# Sheet2.net
KiCad netlist of a schematic drawn in Altium Designer
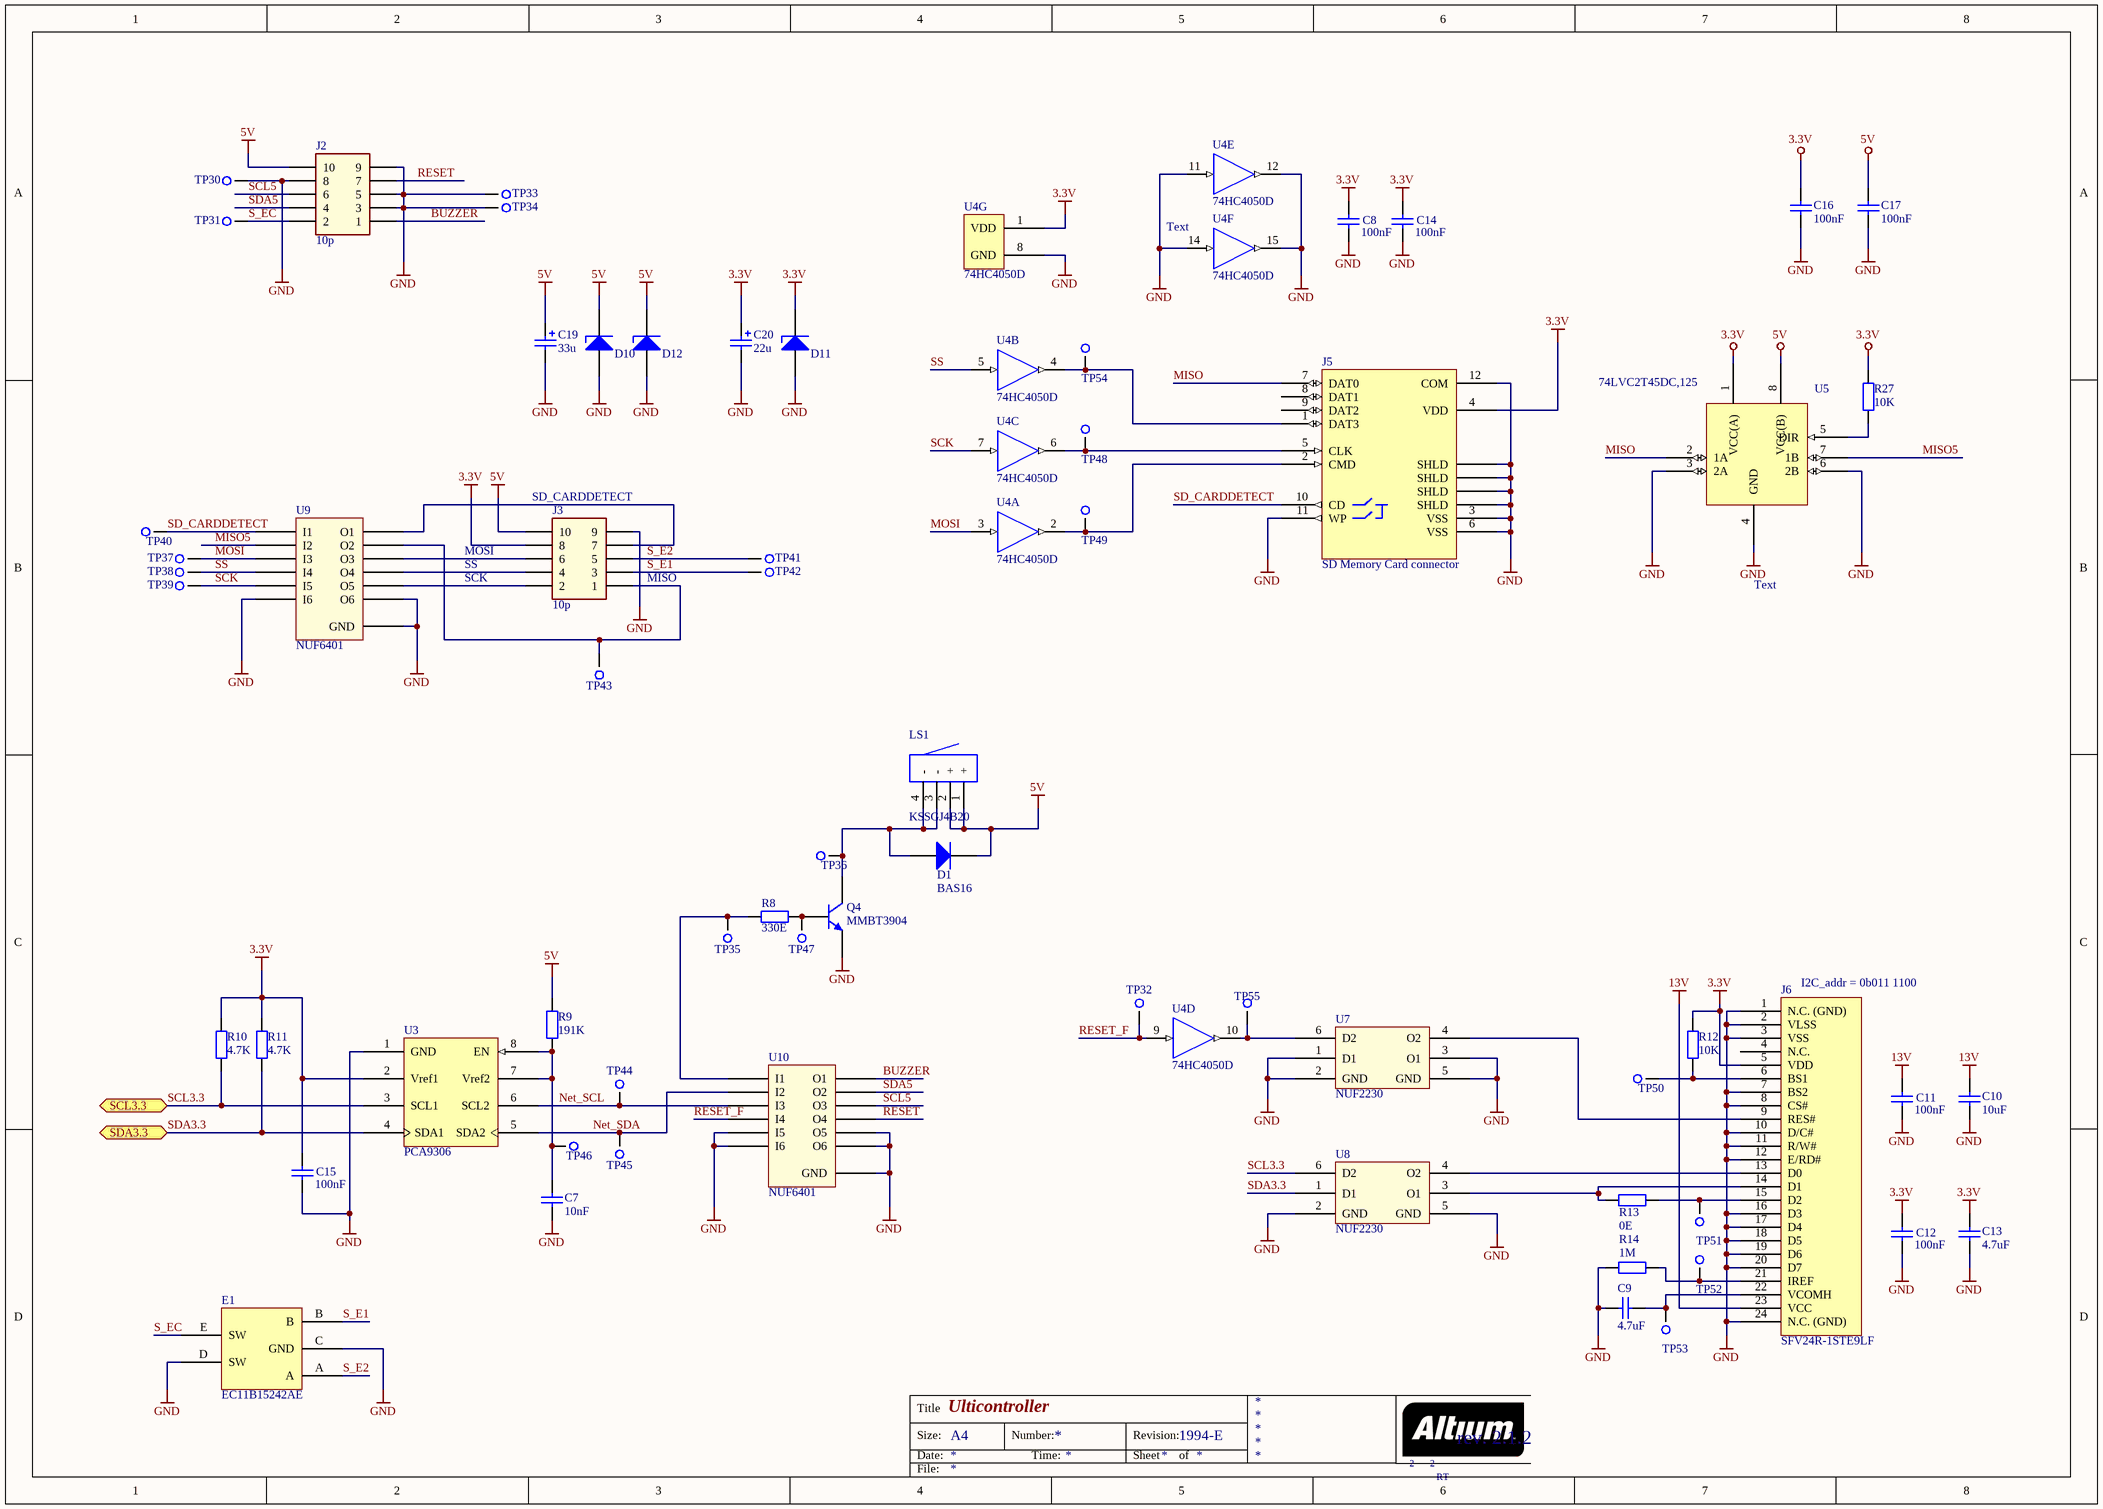
[diagram p0: Sheet2.SchDoc]

(export (version "E")
  (design (tool "Eeschema 10.0.6"))
  (components
    (comp (ref "C7")
      (value "10nF")
      (footprint "C0805 (2012)")
      (description "Cap 10nF X7R 0805 10% 100V")
      (fields (field (name "MFG") "AVX"))
      (libsource (lib "Faber_SCH_lib") (part "Cap 10nF X7R 0805"))
    )
    (comp (ref "C8")
      (value "100nF")
      (footprint "C0805 (2012)")
      (description "Cap 100nF X7R 0805 10% 100V")
      (fields (field (name "MFG") "AVX"))
      (libsource (lib "Faber_SCH_lib") (part "Cap 100nF X7R 0805"))
    )
    (comp (ref "C9")
      (value "4.7uF")
      (footprint "C1206 (3216)")
      (description "Cap 4.7uF 1206 X7R 10% 25V")
      (fields (field (name "MFG") "TDK"))
      (libsource (lib "Faber_SCH_lib") (part "Cap 4.7uF X7R 1206"))
    )
    (comp (ref "C10")
      (value "10uF")
      (footprint "C1206 (3216)")
      (description "Cap 10uF 1206 X7R 10% 25V")
      (fields (field (name "MFG") "KEMET"))
      (libsource (lib "Faber_SCH_lib") (part "Cap 10uF X7R 1206"))
    )
    (comp (ref "C11")
      (value "100nF")
      (footprint "C0805 (2012)")
      (description "Cap 100nF X7R 0805 10% 100V")
      (fields (field (name "MFG") "AVX"))
      (libsource (lib "Faber_SCH_lib") (part "Cap 100nF X7R 0805"))
    )
    (comp (ref "C12")
      (value "100nF")
      (footprint "C0805 (2012)")
      (description "Cap 100nF X7R 0805 10% 100V")
      (fields (field (name "MFG") "AVX"))
      (libsource (lib "Faber_SCH_lib") (part "Cap 100nF X7R 0805"))
    )
    (comp (ref "C13")
      (value "4.7uF")
      (footprint "C1206 (3216)")
      (description "Cap 4.7uF 1206 X7R 10% 25V")
      (fields (field (name "MFG") "TDK"))
      (libsource (lib "Faber_SCH_lib") (part "Cap 4.7uF X7R 1206"))
    )
    (comp (ref "C14")
      (value "100nF")
      (footprint "C0805 (2012)")
      (description "Cap 100nF X7R 0805 10% 100V")
      (fields (field (name "MFG") "AVX"))
      (libsource (lib "Faber_SCH_lib") (part "Cap 100nF X7R 0805"))
    )
    (comp (ref "C15")
      (value "100nF")
      (footprint "C0805 (2012)")
      (description "Cap 100nF X7R 0805 10% 100V")
      (fields (field (name "MFG") "AVX"))
      (libsource (lib "Faber_SCH_lib") (part "Cap 100nF X7R 0805"))
    )
    (comp (ref "C16")
      (value "100nF")
      (footprint "C0805 (2012)")
      (description "Cap 100nF X7R 0805 10% 100V")
      (fields (field (name "MFG") "AVX"))
      (libsource (lib "Faber_SCH_lib") (part "Cap 100nF X7R 0805"))
    )
    (comp (ref "C17")
      (value "100nF")
      (footprint "C0805 (2012)")
      (description "Cap 100nF X7R 0805 10% 100V")
      (fields (field (name "MFG") "AVX"))
      (libsource (lib "Faber_SCH_lib") (part "Cap 100nF X7R 0805"))
    )
    (comp (ref "C19")
      (value "33u")
      (footprint "CAPAE5543X61M")
      (description "CAP ALUM 33UF 20% 10V SMD")
      (fields (field (name "MFG") "Panasonic Electronic Components") (field (name "TOLERANCE") "±20%"))
      (libsource (lib "UltiController") (part "Cap 33uF"))
    )
    (comp (ref "C20")
      (value "22u")
      (footprint "CAPAE5543X61M")
      (description "CAP ALUM 22UF 20% 6.3V SMD")
      (fields (field (name "MFG") "Panasonic Electronic Components") (field (name "TOLERANCE") "±20%"))
      (libsource (lib "UltiController") (part "Cap 22uF"))
    )
    (comp (ref "D1")
      (value "BAS16")
      (footprint "IC SOT23")
      (description "Diode BAS16  SOT23 85V 215MA")
      (fields (field (name "MFG") "NXP"))
      (libsource (lib "Faber_SCH_lib") (part "Diode BAS16"))
    )
    (comp (ref "D10")
      (value "ESD9X5.0ST5G")
      (footprint "SODFL100X40-2N")
      (description "TVS DIODE 5VWM 12.3VC SOD923")
      (fields (field (name "MFG") "ON Semiconductor"))
      (libsource (lib "Olimex interface board") (part "ESD9X5.0ST5G"))
    )
    (comp (ref "D11")
      (value "ESD9X3.3ST5G")
      (footprint "SODFL100X40-2N")
      (description "TVS DIODE 3.3VWM 10.4VC SOD923")
      (fields (field (name "MFG") "ON Semiconductor"))
      (libsource (lib "Olimex interface board") (part "ESD9X3.3ST5G"))
    )
    (comp (ref "D12")
      (value "ESD9X5.0ST5G")
      (footprint "SODFL100X40-2N")
      (description "TVS DIODE 5VWM 12.3VC SOD923")
      (fields (field (name "MFG") "ON Semiconductor"))
      (libsource (lib "Olimex interface board") (part "ESD9X5.0ST5G"))
    )
    (comp (ref "E1")
      (value "EC11B15242AE")
      (footprint "Misc EC11B15242AE")
      (description "Misc EC11B15242AE encoder horiz")
      (fields (field (name "MFG") "ALPS"))
      (libsource (lib "Faber_SCH_lib") (part "Misc EC11B15242AE"))
    )
    (comp (ref "J2")
      (value "10p")
      (footprint "HEADER 10P right angle")
      (description "Header 2x5p right angle 2.54mm")
      (fields (field (name "MFG") "WURTH ELEKTRONIK"))
      (libsource (lib "Faber_SCH_lib") (part "Header 10p"))
    )
    (comp (ref "J3")
      (value "10p")
      (footprint "HEADER 10P right angle")
      (description "Header 2x5p right angle 2.54mm")
      (fields (field (name "MFG") "WURTH ELEKTRONIK"))
      (libsource (lib "Faber_SCH_lib") (part "Header 10p"))
    )
    (comp (ref "J5")
      (value "SD Memory Card connector")
      (footprint "CON SD-Card")
      (description "Connector Std,reverse SD Memory Card connector")
      (fields (field (name "MFG") "HRS (HIROSE)"))
      (libsource (lib "Faber_SCH_lib") (part "Connector SD-Card-Hirose"))
    )
    (comp (ref "J6")
      (value "SFV24R-1STE9LF")
      (footprint "Con SFV24R-1STE9LF")
      (description "Connector FPC/FFC 0.5mm R/A 24p SMD")
      (fields (field (name "MFG") "FCI"))
      (libsource (lib "Faber_SCH_lib") (part "Connector SFV24R-1STE9LF"))
    )
    (comp (ref "LS1")
      (value "KSSGJ4B20")
      (footprint "Buzzer KSSGJ4B20")
      (description "Buzzer KSSGJ4B20 SMD")
      (fields (field (name "MFG") "KINGSTATE"))
      (libsource (lib "Faber_SCH_lib") (part "Buzzer KSSGJ4B20"))
    )
    (comp (ref "Q4")
      (value "MMBT3904")
      (footprint "IC SOT23")
      (description "NPN MMBT3904 SOT-23 200mA")
      (fields (field (name "MFG") "NXP"))
      (libsource (lib "Faber_SCH_lib") (part "NPN MMBT3904"))
    )
    (comp (ref "R8")
      (value "330E")
      (footprint "R0805 (2012)")
      (description "Res 330E 0805 1% 100mW")
      (fields (field (name "MFG") "MULTICOMP"))
      (libsource (lib "Faber_SCH_lib") (part "Res 330E 0805"))
    )
    (comp (ref "R9")
      (value "191K")
      (footprint "R0805 (2012)")
      (description "Res 191K 0805 1% 125mW")
      (fields (field (name "MFG") "VISHAY DRALORIC"))
      (libsource (lib "Faber_SCH_lib") (part "Res 191K 0805"))
    )
    (comp (ref "R10")
      (value "4.7K")
      (footprint "R0805 (2012)")
      (description "Res 4.7K 0805 1% 100mW")
      (fields (field (name "MFG") "MULTICOMP"))
      (libsource (lib "Faber_SCH_lib") (part "Res 4.7K 0805"))
    )
    (comp (ref "R11")
      (value "4.7K")
      (footprint "R0805 (2012)")
      (description "Res 4.7K 0805 1% 100mW")
      (fields (field (name "MFG") "MULTICOMP"))
      (libsource (lib "Faber_SCH_lib") (part "Res 4.7K 0805"))
    )
    (comp (ref "R12")
      (value "10K")
      (footprint "R0805 (2012)")
      (description "Res 10K 0805 1% 100mW")
      (fields (field (name "MFG") "MULTICOMP"))
      (libsource (lib "Faber_SCH_lib") (part "Res 10K 0805"))
    )
    (comp (ref "R13")
      (value "0E")
      (footprint "R0805 (2012)")
      (description "Res 0E 0805 1% 100mW")
      (fields (field (name "MFG") "MULTICOMP"))
      (libsource (lib "Faber_SCH_lib") (part "Res 0E 0805"))
    )
    (comp (ref "R14")
      (value "1M")
      (footprint "R0805 (2012)")
      (description "Res 1M 0805 1% 100mW")
      (fields (field (name "MFG") "MULTICOMP"))
      (libsource (lib "Faber_SCH_lib") (part "Res 1M 0805"))
    )
    (comp (ref "R27")
      (value "10K")
      (footprint "R0805 (2012)")
      (description "Res 10K 0805 1% 100mW")
      (fields (field (name "MFG") "MULTICOMP"))
      (libsource (lib "Faber_SCH_lib") (part "Res 10K 0805"))
    )
    (comp (ref "TP30")
      (value "2mm")
      (footprint "TESTPOINT 2mm")
      (description "Testpoint, 2mm, round")
      (libsource (lib "Faber_SCH_lib") (part "Testpoint, 2mm, round"))
    )
    (comp (ref "TP31")
      (value "2mm")
      (footprint "TESTPOINT 2mm")
      (description "Testpoint, 2mm, round")
      (libsource (lib "Faber_SCH_lib") (part "Testpoint, 2mm, round"))
    )
    (comp (ref "TP32")
      (value "2mm")
      (footprint "TESTPOINT 2mm")
      (description "Testpoint, 2mm, round")
      (libsource (lib "Faber_SCH_lib") (part "Testpoint, 2mm, round"))
    )
    (comp (ref "TP33")
      (value "2mm")
      (footprint "TESTPOINT 2mm")
      (description "Testpoint, 2mm, round")
      (libsource (lib "Faber_SCH_lib") (part "Testpoint, 2mm, round"))
    )
    (comp (ref "TP34")
      (value "2mm")
      (footprint "TESTPOINT 2mm")
      (description "Testpoint, 2mm, round")
      (libsource (lib "Faber_SCH_lib") (part "Testpoint, 2mm, round"))
    )
    (comp (ref "TP35")
      (value "2mm")
      (footprint "TESTPOINT 2mm")
      (description "Testpoint, 2mm, round")
      (libsource (lib "Faber_SCH_lib") (part "Testpoint, 2mm, round"))
    )
    (comp (ref "TP36")
      (value "2mm")
      (footprint "TESTPOINT 2mm")
      (description "Testpoint, 2mm, round")
      (libsource (lib "Faber_SCH_lib") (part "Testpoint, 2mm, round"))
    )
    (comp (ref "TP37")
      (value "2mm")
      (footprint "TESTPOINT 2mm")
      (description "Testpoint, 2mm, round")
      (libsource (lib "Faber_SCH_lib") (part "Testpoint, 2mm, round"))
    )
    (comp (ref "TP38")
      (value "2mm")
      (footprint "TESTPOINT 2mm")
      (description "Testpoint, 2mm, round")
      (libsource (lib "Faber_SCH_lib") (part "Testpoint, 2mm, round"))
    )
    (comp (ref "TP39")
      (value "2mm")
      (footprint "TESTPOINT 2mm")
      (description "Testpoint, 2mm, round")
      (libsource (lib "Faber_SCH_lib") (part "Testpoint, 2mm, round"))
    )
    (comp (ref "TP40")
      (value "2mm")
      (footprint "TESTPOINT 2mm")
      (description "Testpoint, 2mm, round")
      (libsource (lib "Faber_SCH_lib") (part "Testpoint, 2mm, round"))
    )
    (comp (ref "TP41")
      (value "2mm")
      (footprint "TESTPOINT 2mm")
      (description "Testpoint, 2mm, round")
      (libsource (lib "Faber_SCH_lib") (part "Testpoint, 2mm, round"))
    )
    (comp (ref "TP42")
      (value "2mm")
      (footprint "TESTPOINT 2mm")
      (description "Testpoint, 2mm, round")
      (libsource (lib "Faber_SCH_lib") (part "Testpoint, 2mm, round"))
    )
    (comp (ref "TP43")
      (value "2mm")
      (footprint "TESTPOINT 2mm")
      (description "Testpoint, 2mm, round")
      (libsource (lib "Faber_SCH_lib") (part "Testpoint, 2mm, round"))
    )
    (comp (ref "TP44")
      (value "2mm")
      (footprint "TESTPOINT 2mm")
      (description "Testpoint, 2mm, round")
      (libsource (lib "Faber_SCH_lib") (part "Testpoint, 2mm, round"))
    )
    (comp (ref "TP45")
      (value "2mm")
      (footprint "TESTPOINT 2mm")
      (description "Testpoint, 2mm, round")
      (libsource (lib "Faber_SCH_lib") (part "Testpoint, 2mm, round"))
    )
    (comp (ref "TP46")
      (value "2mm")
      (footprint "TESTPOINT 2mm")
      (description "Testpoint, 2mm, round")
      (libsource (lib "Faber_SCH_lib") (part "Testpoint, 2mm, round"))
    )
    (comp (ref "TP47")
      (value "2mm")
      (footprint "TESTPOINT 2mm")
      (description "Testpoint, 2mm, round")
      (libsource (lib "Faber_SCH_lib") (part "Testpoint, 2mm, round"))
    )
    (comp (ref "TP48")
      (value "2mm")
      (footprint "TESTPOINT 2mm")
      (description "Testpoint, 2mm, round")
      (libsource (lib "Faber_SCH_lib") (part "Testpoint, 2mm, round"))
    )
    (comp (ref "TP49")
      (value "2mm")
      (footprint "TESTPOINT 2mm")
      (description "Testpoint, 2mm, round")
      (libsource (lib "Faber_SCH_lib") (part "Testpoint, 2mm, round"))
    )
    (comp (ref "TP50")
      (value "2mm")
      (footprint "TESTPOINT 2mm")
      (description "Testpoint, 2mm, round")
      (libsource (lib "Faber_SCH_lib") (part "Testpoint, 2mm, round"))
    )
    (comp (ref "TP51")
      (value "2mm")
      (footprint "TESTPOINT 2mm")
      (description "Testpoint, 2mm, round")
      (libsource (lib "Faber_SCH_lib") (part "Testpoint, 2mm, round"))
    )
    (comp (ref "TP52")
      (value "2mm")
      (footprint "TESTPOINT 2mm")
      (description "Testpoint, 2mm, round")
      (libsource (lib "Faber_SCH_lib") (part "Testpoint, 2mm, round"))
    )
    (comp (ref "TP53")
      (value "2mm")
      (footprint "TESTPOINT 2mm")
      (description "Testpoint, 2mm, round")
      (libsource (lib "Faber_SCH_lib") (part "Testpoint, 2mm, round"))
    )
    (comp (ref "TP54")
      (value "2mm")
      (footprint "TESTPOINT 2mm")
      (description "Testpoint, 2mm, round")
      (libsource (lib "Faber_SCH_lib") (part "Testpoint, 2mm, round"))
    )
    (comp (ref "TP55")
      (value "2mm")
      (footprint "TESTPOINT 2mm")
      (description "Testpoint, 2mm, round")
      (libsource (lib "Faber_SCH_lib") (part "Testpoint, 2mm, round"))
    )
    (comp (ref "U3")
      (value "PCA9306")
      (footprint "IC SSOP-8")
      (description "IC PCA9306 Voltage Level translator")
      (fields (field (name "MFG") "TEXAS INSTRUMENTS"))
      (libsource (lib "Faber_SCH_lib") (part "IC PCA9306"))
    )
    (comp (ref "U4")
      (value "74HC4050D")
      (footprint "IC SOIC-16")
      (description "IC Hex Non-Inverting Buffer/Logic-Level Down Converter")
      (fields (field (name "MFG") "NXP"))
      (libsource (lib "Faber_SCH_lib") (part "IC 74HC4050D"))
    )
    (comp (ref "U5")
      (value "74LVC2T45DC,125")
      (footprint "TSSOP50P310X100-8N")
      (description "2-bit translaing transceiver")
      (fields (field (name "MFG") "NXP"))
      (libsource (lib "Olimex interface board") (part "74LVC2T45DC,125"))
    )
    (comp (ref "U7")
      (value "NUF2230")
      (footprint "SOTFL50P160X60-6N")
      (fields (field (name "MFG") "ON Semiconductor"))
      (libsource (lib "printehead") (part "NUF2230"))
    )
    (comp (ref "U8")
      (value "NUF2230")
      (footprint "SOTFL50P160X60-6N")
      (fields (field (name "MFG") "ON Semiconductor"))
      (libsource (lib "printehead") (part "NUF2230"))
    )
    (comp (ref "U9")
      (value "NUF6401")
      (footprint "SON50P140X100_HS-13N")
      (fields (field (name "MFG") "ON Semiconductor"))
      (libsource (lib "UltiController") (part "NUF6401"))
    )
    (comp (ref "U10")
      (value "NUF6401")
      (footprint "SON50P140X100_HS-13N")
      (fields (field (name "MFG") "ON Semiconductor"))
      (libsource (lib "UltiController") (part "NUF6401"))
    )
  )
  (nets
    (net (code "1") (name "/BUZZER") (class "Default")
      (node (ref "J2") (pin "1") (pinfunction "1_1") (pintype "passive"))
      (node (ref "U10") (pin "12") (pinfunction "O1_12") (pintype "passive"))
    )
    (net (code "2") (name "/MISO") (class "Default")
      (node (ref "J5") (pin "7") (pinfunction "DAT0_7") (pintype "bidirectional"))
      (node (ref "U5") (pin "2") (pinfunction "1A_2") (pintype "bidirectional"))
    )
    (net (code "3") (name "/MISO5") (class "Default")
      (node (ref "U5") (pin "7") (pinfunction "1B_7") (pintype "bidirectional"))
      (node (ref "U9") (pin "2") (pinfunction "I2_2") (pintype "passive"))
    )
    (net (code "4") (name "/MOSI") (class "Default")
      (node (ref "TP37") (pin "1") (pinfunction "1_1") (pintype "passive"))
      (node (ref "U4") (pin "3") (pinfunction "A_3") (pintype "input"))
      (node (ref "U9") (pin "3") (pinfunction "I3_3") (pintype "passive"))
    )
    (net (code "5") (name "/Net_SCL") (class "Default")
      (node (ref "TP44") (pin "1") (pinfunction "1_1") (pintype "passive"))
      (node (ref "U10") (pin "3") (pinfunction "I3_3") (pintype "passive"))
      (node (ref "U3") (pin "6") (pinfunction "SCL2_6") (pintype "passive"))
    )
    (net (code "6") (name "/Net_SDA") (class "Default")
      (node (ref "TP45") (pin "1") (pinfunction "1_1") (pintype "passive"))
      (node (ref "U10") (pin "2") (pinfunction "I2_2") (pintype "passive"))
      (node (ref "U3") (pin "5") (pinfunction "SDA2_5") (pintype "passive"))
    )
    (net (code "7") (name "/RESET") (class "Default")
      (node (ref "J2") (pin "7") (pinfunction "7_7") (pintype "passive"))
      (node (ref "U10") (pin "9") (pinfunction "O4_9") (pintype "passive"))
    )
    (net (code "8") (name "/RESET_F") (class "Default")
      (node (ref "TP32") (pin "1") (pinfunction "1_1") (pintype "passive"))
      (node (ref "U10") (pin "4") (pinfunction "I4_4") (pintype "passive"))
      (node (ref "U4") (pin "9") (pinfunction "A_9") (pintype "input"))
    )
    (net (code "9") (name "/SCK") (class "Default")
      (node (ref "TP39") (pin "1") (pinfunction "1_1") (pintype "passive"))
      (node (ref "U4") (pin "7") (pinfunction "A_7") (pintype "input"))
      (node (ref "U9") (pin "5") (pinfunction "I5_5") (pintype "passive"))
    )
    (net (code "10") (name "/SCL3.3") (class "Default")
      (node (ref "R10") (pin "1") (pinfunction "1_1") (pintype "passive"))
      (node (ref "U3") (pin "3") (pinfunction "SCL1_3") (pintype "passive"))
      (node (ref "U8") (pin "6") (pinfunction "D2_6") (pintype "passive"))
    )
    (net (code "11") (name "/SCL5") (class "Default")
      (node (ref "J2") (pin "6") (pinfunction "6_6") (pintype "passive"))
      (node (ref "U10") (pin "10") (pinfunction "O3_10") (pintype "passive"))
    )
    (net (code "12") (name "/SDA3.3") (class "Default")
      (node (ref "R11") (pin "1") (pinfunction "1_1") (pintype "passive"))
      (node (ref "U3") (pin "4") (pinfunction "SDA1_4") (pintype "passive"))
      (node (ref "U8") (pin "1") (pinfunction "D1_1") (pintype "passive"))
    )
    (net (code "13") (name "/SDA5") (class "Default")
      (node (ref "J2") (pin "4") (pinfunction "4_4") (pintype "passive"))
      (node (ref "U10") (pin "11") (pinfunction "O2_11") (pintype "passive"))
    )
    (net (code "14") (name "/SD_CARDDETECT") (class "Default")
      (node (ref "J5") (pin "10") (pinfunction "CD_10") (pintype "output"))
      (node (ref "TP40") (pin "1") (pinfunction "1_1") (pintype "passive"))
      (node (ref "U9") (pin "1") (pinfunction "I1_1") (pintype "passive"))
    )
    (net (code "15") (name "/SS") (class "Default")
      (node (ref "TP38") (pin "1") (pinfunction "1_1") (pintype "passive"))
      (node (ref "U4") (pin "5") (pinfunction "A_5") (pintype "input"))
      (node (ref "U9") (pin "4") (pinfunction "I4_4") (pintype "passive"))
    )
    (net (code "16") (name "/S_E1") (class "Default")
      (node (ref "E1") (pin "B") (pinfunction "B_B") (pintype "passive"))
      (node (ref "J3") (pin "3") (pinfunction "3_3") (pintype "passive"))
      (node (ref "TP42") (pin "1") (pinfunction "1_1") (pintype "passive"))
    )
    (net (code "17") (name "/S_E2") (class "Default")
      (node (ref "E1") (pin "A") (pinfunction "A_A") (pintype "passive"))
      (node (ref "J3") (pin "5") (pinfunction "5_5") (pintype "passive"))
      (node (ref "TP41") (pin "1") (pinfunction "1_1") (pintype "passive"))
    )
    (net (code "18") (name "/S_EC") (class "Default")
      (node (ref "E1") (pin "E") (pinfunction "SW_E") (pintype "passive"))
      (node (ref "J2") (pin "2") (pinfunction "2_2") (pintype "passive"))
      (node (ref "TP31") (pin "1") (pinfunction "1_1") (pintype "passive"))
    )
    (net (code "19") (name "3.3V") (class "Default")
      (node (ref "C12") (pin "2") (pinfunction "2_2") (pintype "passive"))
      (node (ref "C13") (pin "1") (pinfunction "1_1") (pintype "passive"))
      (node (ref "C14") (pin "2") (pinfunction "2_2") (pintype "passive"))
      (node (ref "C15") (pin "2") (pinfunction "2_2") (pintype "passive"))
      (node (ref "C16") (pin "1") (pinfunction "1_1") (pintype "passive"))
      (node (ref "C20") (pin "1") (pinfunction "1_1") (pintype "passive"))
      (node (ref "C8") (pin "2") (pinfunction "2_2") (pintype "passive"))
      (node (ref "D11") (pin "1") (pinfunction "K_1") (pintype "passive"))
      (node (ref "J3") (pin "8") (pinfunction "8_8") (pintype "passive"))
      (node (ref "J5") (pin "4") (pinfunction "VDD_4") (pintype "power_in"))
      (node (ref "J6") (pin "5") (pinfunction "VDD_5") (pintype "passive"))
      (node (ref "R10") (pin "2") (pinfunction "2_2") (pintype "passive"))
      (node (ref "R11") (pin "2") (pinfunction "2_2") (pintype "passive"))
      (node (ref "R12") (pin "2") (pinfunction "2_2") (pintype "passive"))
      (node (ref "R27") (pin "2") (pinfunction "2_2") (pintype "passive"))
      (node (ref "U3") (pin "2") (pinfunction "Vref1_2") (pintype "power_in"))
      (node (ref "U4") (pin "1") (pinfunction "VDD_1") (pintype "power_in"))
      (node (ref "U5") (pin "1") (pinfunction "VCC(A)_1") (pintype "power_in"))
    )
    (net (code "20") (name "5V") (class "Default")
      (node (ref "C17") (pin "1") (pinfunction "1_1") (pintype "passive"))
      (node (ref "C19") (pin "1") (pinfunction "1_1") (pintype "passive"))
      (node (ref "D1") (pin "3") (pinfunction "K_3") (pintype "passive"))
      (node (ref "D10") (pin "1") (pinfunction "K_1") (pintype "passive"))
      (node (ref "D12") (pin "1") (pinfunction "K_1") (pintype "passive"))
      (node (ref "J2") (pin "10") (pinfunction "10_10") (pintype "passive"))
      (node (ref "J3") (pin "10") (pinfunction "10_10") (pintype "passive"))
      (node (ref "LS1") (pin "1") (pinfunction "+_1") (pintype "passive"))
      (node (ref "LS1") (pin "2") (pinfunction "+_2") (pintype "passive"))
      (node (ref "R9") (pin "2") (pinfunction "2_2") (pintype "passive"))
      (node (ref "U5") (pin "8") (pinfunction "VCC(B)_8") (pintype "power_in"))
    )
    (net (code "21") (name "13V") (class "Default")
      (node (ref "C10") (pin "2") (pinfunction "2_2") (pintype "passive"))
      (node (ref "C11") (pin "2") (pinfunction "2_2") (pintype "passive"))
      (node (ref "J6") (pin "23") (pinfunction "VCC_23") (pintype "passive"))
    )
    (net (code "22") (name "GND") (class "Default")
      (node (ref "C10") (pin "1") (pinfunction "1_1") (pintype "passive"))
      (node (ref "C11") (pin "1") (pinfunction "1_1") (pintype "passive"))
      (node (ref "C12") (pin "1") (pinfunction "1_1") (pintype "passive"))
      (node (ref "C13") (pin "2") (pinfunction "2_2") (pintype "passive"))
      (node (ref "C14") (pin "1") (pinfunction "1_1") (pintype "passive"))
      (node (ref "C15") (pin "1") (pinfunction "1_1") (pintype "passive"))
      (node (ref "C16") (pin "2") (pinfunction "2_2") (pintype "passive"))
      (node (ref "C17") (pin "2") (pinfunction "2_2") (pintype "passive"))
      (node (ref "C19") (pin "2") (pinfunction "2_2") (pintype "passive"))
      (node (ref "C20") (pin "2") (pinfunction "2_2") (pintype "passive"))
      (node (ref "C7") (pin "1") (pinfunction "1_1") (pintype "passive"))
      (node (ref "C8") (pin "1") (pinfunction "1_1") (pintype "passive"))
      (node (ref "C9") (pin "2") (pinfunction "2_2") (pintype "passive"))
      (node (ref "D10") (pin "2") (pinfunction "A_2") (pintype "passive"))
      (node (ref "D11") (pin "2") (pinfunction "A_2") (pintype "passive"))
      (node (ref "D12") (pin "2") (pinfunction "A_2") (pintype "passive"))
      (node (ref "E1") (pin "C") (pinfunction "GND_C") (pintype "passive"))
      (node (ref "E1") (pin "D") (pinfunction "SW_D") (pintype "passive"))
      (node (ref "J2") (pin "3") (pinfunction "3_3") (pintype "passive"))
      (node (ref "J2") (pin "5") (pinfunction "5_5") (pintype "passive"))
      (node (ref "J2") (pin "8") (pinfunction "8_8") (pintype "passive"))
      (node (ref "J2") (pin "9") (pinfunction "9_9") (pintype "passive"))
      (node (ref "J3") (pin "9") (pinfunction "9_9") (pintype "passive"))
      (node (ref "J5") (pin "11") (pinfunction "WP_11") (pintype "output"))
      (node (ref "J5") (pin "12") (pinfunction "COM_12") (pintype "power_in"))
      (node (ref "J5") (pin "3") (pinfunction "VSS_3") (pintype "power_in"))
      (node (ref "J5") (pin "6") (pinfunction "VSS_6") (pintype "power_in"))
      (node (ref "J5") (pin "A") (pinfunction "SHLD_A") (pintype "power_in"))
      (node (ref "J5") (pin "B") (pinfunction "SHLD_B") (pintype "power_in"))
      (node (ref "J5") (pin "C") (pinfunction "SHLD_C") (pintype "power_in"))
      (node (ref "J5") (pin "D") (pinfunction "SHLD_D") (pintype "power_in"))
      (node (ref "J6") (pin "1") (pinfunction "N.C._(GND)_1") (pintype "passive"))
      (node (ref "J6") (pin "10") (pinfunction "D/C#_10") (pintype "passive"))
      (node (ref "J6") (pin "11") (pinfunction "R/W#_11") (pintype "passive"))
      (node (ref "J6") (pin "12") (pinfunction "E/RD#_12") (pintype "passive"))
      (node (ref "J6") (pin "16") (pinfunction "D3_16") (pintype "passive"))
      (node (ref "J6") (pin "17") (pinfunction "D4_17") (pintype "passive"))
      (node (ref "J6") (pin "18") (pinfunction "D5_18") (pintype "passive"))
      (node (ref "J6") (pin "19") (pinfunction "D6_19") (pintype "passive"))
      (node (ref "J6") (pin "2") (pinfunction "VLSS_2") (pintype "passive"))
      (node (ref "J6") (pin "20") (pinfunction "D7_20") (pintype "passive"))
      (node (ref "J6") (pin "24") (pinfunction "N.C._(GND)_24") (pintype "passive"))
      (node (ref "J6") (pin "3") (pinfunction "VSS_3") (pintype "passive"))
      (node (ref "J6") (pin "7") (pinfunction "BS2_7") (pintype "passive"))
      (node (ref "J6") (pin "8") (pinfunction "CS#_8") (pintype "passive"))
      (node (ref "Q4") (pin "2") (pinfunction "E_2") (pintype "passive"))
      (node (ref "R14") (pin "1") (pinfunction "1_1") (pintype "passive"))
      (node (ref "TP30") (pin "1") (pinfunction "1_1") (pintype "passive"))
      (node (ref "TP33") (pin "1") (pinfunction "1_1") (pintype "passive"))
      (node (ref "TP34") (pin "1") (pinfunction "1_1") (pintype "passive"))
      (node (ref "U10") (pin "13") (pinfunction "GND_13") (pintype "passive"))
      (node (ref "U10") (pin "5") (pinfunction "I5_5") (pintype "passive"))
      (node (ref "U10") (pin "6") (pinfunction "I6_6") (pintype "passive"))
      (node (ref "U10") (pin "7") (pinfunction "O6_7") (pintype "passive"))
      (node (ref "U10") (pin "8") (pinfunction "O5_8") (pintype "passive"))
      (node (ref "U3") (pin "1") (pinfunction "GND_1") (pintype "power_in"))
      (node (ref "U4") (pin "11") (pinfunction "A_11") (pintype "input"))
      (node (ref "U4") (pin "12") (pinfunction "Y_12") (pintype "output"))
      (node (ref "U4") (pin "14") (pinfunction "A_14") (pintype "input"))
      (node (ref "U4") (pin "15") (pinfunction "Y_15") (pintype "output"))
      (node (ref "U4") (pin "8") (pinfunction "GND_8") (pintype "power_in"))
      (node (ref "U5") (pin "3") (pinfunction "2A_3") (pintype "bidirectional"))
      (node (ref "U5") (pin "4") (pinfunction "GND_4") (pintype "power_in"))
      (node (ref "U5") (pin "6") (pinfunction "2B_6") (pintype "bidirectional"))
      (node (ref "U7") (pin "1") (pinfunction "D1_1") (pintype "passive"))
      (node (ref "U7") (pin "2") (pinfunction "GND_2") (pintype "passive"))
      (node (ref "U7") (pin "3") (pinfunction "O1_3") (pintype "passive"))
      (node (ref "U7") (pin "5") (pinfunction "GND_5") (pintype "passive"))
      (node (ref "U8") (pin "2") (pinfunction "GND_2") (pintype "passive"))
      (node (ref "U8") (pin "5") (pinfunction "GND_5") (pintype "passive"))
      (node (ref "U9") (pin "13") (pinfunction "GND_13") (pintype "passive"))
      (node (ref "U9") (pin "6") (pinfunction "I6_6") (pintype "passive"))
      (node (ref "U9") (pin "7") (pinfunction "O6_7") (pintype "passive"))
    )
    (net (code "23") (name "Net-(D1-A)") (class "Default")
      (node (ref "D1") (pin "1") (pinfunction "A_1") (pintype "passive"))
      (node (ref "LS1") (pin "3") (pinfunction "-_3") (pintype "passive"))
      (node (ref "LS1") (pin "4") (pinfunction "-_4") (pintype "passive"))
      (node (ref "Q4") (pin "3") (pinfunction "C_3") (pintype "passive"))
      (node (ref "TP36") (pin "1") (pinfunction "1_1") (pintype "passive"))
    )
    (net (code "24") (name "Net-(J5-CLK)") (class "Default")
      (node (ref "J5") (pin "5") (pinfunction "CLK_5") (pintype "input"))
      (node (ref "TP48") (pin "1") (pinfunction "1_1") (pintype "passive"))
      (node (ref "U4") (pin "6") (pinfunction "Y_6") (pintype "output"))
    )
    (net (code "25") (name "Net-(J5-CMD)") (class "Default")
      (node (ref "J5") (pin "2") (pinfunction "CMD_2") (pintype "input"))
      (node (ref "TP49") (pin "1") (pinfunction "1_1") (pintype "passive"))
      (node (ref "U4") (pin "2") (pinfunction "Y_2") (pintype "output"))
    )
    (net (code "26") (name "Net-(J5-DAT3)") (class "Default")
      (node (ref "J5") (pin "1") (pinfunction "DAT3_1") (pintype "bidirectional"))
      (node (ref "TP54") (pin "1") (pinfunction "1_1") (pintype "passive"))
      (node (ref "U4") (pin "4") (pinfunction "Y_4") (pintype "output"))
    )
    (net (code "27") (name "Net-(J6-BS1)") (class "Default")
      (node (ref "J6") (pin "6") (pinfunction "BS1_6") (pintype "passive"))
      (node (ref "R12") (pin "1") (pinfunction "1_1") (pintype "passive"))
      (node (ref "TP50") (pin "1") (pinfunction "1_1") (pintype "passive"))
    )
    (net (code "28") (name "Net-(J6-D0)") (class "Default")
      (node (ref "J6") (pin "13") (pinfunction "D0_13") (pintype "passive"))
      (node (ref "U8") (pin "4") (pinfunction "O2_4") (pintype "passive"))
    )
    (net (code "29") (name "Net-(J6-D1)") (class "Default")
      (node (ref "J6") (pin "14") (pinfunction "D1_14") (pintype "passive"))
      (node (ref "R13") (pin "1") (pinfunction "1_1") (pintype "passive"))
      (node (ref "U8") (pin "3") (pinfunction "O1_3") (pintype "passive"))
    )
    (net (code "30") (name "Net-(J6-D2)") (class "Default")
      (node (ref "J6") (pin "15") (pinfunction "D2_15") (pintype "passive"))
      (node (ref "R13") (pin "2") (pinfunction "2_2") (pintype "passive"))
      (node (ref "TP51") (pin "1") (pinfunction "1_1") (pintype "passive"))
    )
    (net (code "31") (name "Net-(J6-IREF)") (class "Default")
      (node (ref "J6") (pin "21") (pinfunction "IREF_21") (pintype "passive"))
      (node (ref "R14") (pin "2") (pinfunction "2_2") (pintype "passive"))
      (node (ref "TP52") (pin "1") (pinfunction "1_1") (pintype "passive"))
    )
    (net (code "32") (name "Net-(J6-RES#)") (class "Default")
      (node (ref "J6") (pin "9") (pinfunction "RES#_9") (pintype "passive"))
      (node (ref "U7") (pin "4") (pinfunction "O2_4") (pintype "passive"))
    )
    (net (code "33") (name "Net-(J6-VCOMH)") (class "Default")
      (node (ref "C9") (pin "1") (pinfunction "1_1") (pintype "passive"))
      (node (ref "J6") (pin "22") (pinfunction "VCOMH_22") (pintype "passive"))
      (node (ref "TP53") (pin "1") (pinfunction "1_1") (pintype "passive"))
    )
    (net (code "34") (name "Net-(Q4-B)") (class "Default")
      (node (ref "Q4") (pin "1") (pinfunction "B_1") (pintype "passive"))
      (node (ref "R8") (pin "2") (pinfunction "2_2") (pintype "passive"))
      (node (ref "TP47") (pin "1") (pinfunction "1_1") (pintype "passive"))
    )
    (net (code "35") (name "Net-(U3-EN)") (class "Default")
      (node (ref "C7") (pin "2") (pinfunction "2_2") (pintype "passive"))
      (node (ref "R9") (pin "1") (pinfunction "1_1") (pintype "passive"))
      (node (ref "TP46") (pin "1") (pinfunction "1_1") (pintype "passive"))
      (node (ref "U3") (pin "7") (pinfunction "Vref2_7") (pintype "power_in"))
      (node (ref "U3") (pin "8") (pinfunction "EN_8") (pintype "input"))
    )
    (net (code "36") (name "Net-(U4D-Y)") (class "Default")
      (node (ref "TP55") (pin "1") (pinfunction "1_1") (pintype "passive"))
      (node (ref "U4") (pin "10") (pinfunction "Y_10") (pintype "output"))
      (node (ref "U7") (pin "6") (pinfunction "D2_6") (pintype "passive"))
    )
    (net (code "37") (name "Net-(U5-DIR)") (class "Default")
      (node (ref "R27") (pin "1") (pinfunction "1_1") (pintype "passive"))
      (node (ref "U5") (pin "5") (pinfunction "DIR_5") (pintype "input"))
    )
    (net (code "38") (name "Net-(U9-O1)") (class "Default")
      (node (ref "J3") (pin "7") (pinfunction "7_7") (pintype "passive"))
      (node (ref "U9") (pin "12") (pinfunction "O1_12") (pintype "passive"))
    )
    (net (code "39") (name "Net-(U9-O2)") (class "Default")
      (node (ref "J3") (pin "1") (pinfunction "1_1") (pintype "passive"))
      (node (ref "TP43") (pin "1") (pinfunction "1_1") (pintype "passive"))
      (node (ref "U9") (pin "11") (pinfunction "O2_11") (pintype "passive"))
    )
    (net (code "40") (name "Net-(U9-O3)") (class "Default")
      (node (ref "J3") (pin "6") (pinfunction "6_6") (pintype "passive"))
      (node (ref "U9") (pin "10") (pinfunction "O3_10") (pintype "passive"))
    )
    (net (code "41") (name "Net-(U9-O4)") (class "Default")
      (node (ref "J3") (pin "4") (pinfunction "4_4") (pintype "passive"))
      (node (ref "U9") (pin "9") (pinfunction "O4_9") (pintype "passive"))
    )
    (net (code "42") (name "Net-(U9-O5)") (class "Default")
      (node (ref "J3") (pin "2") (pinfunction "2_2") (pintype "passive"))
      (node (ref "U9") (pin "8") (pinfunction "O5_8") (pintype "passive"))
    )
    (net (code "43") (name "Net-(U10-I1)") (class "Default")
      (node (ref "R8") (pin "1") (pinfunction "1_1") (pintype "passive"))
      (node (ref "TP35") (pin "1") (pinfunction "1_1") (pintype "passive"))
      (node (ref "U10") (pin "1") (pinfunction "I1_1") (pintype "passive"))
    )
    (net (code "44") (name "unconnected-(J5-DAT1-Pad8)") (class "Default")
      (node (ref "J5") (pin "8") (pinfunction "DAT1_8") (pintype "bidirectional"))
    )
    (net (code "45") (name "unconnected-(J5-DAT2-Pad9)") (class "Default")
      (node (ref "J5") (pin "9") (pinfunction "DAT2_9") (pintype "bidirectional"))
    )
    (net (code "46") (name "unconnected-(J6-N.C.-Pad4)") (class "Default")
      (node (ref "J6") (pin "4") (pinfunction "N.C._4") (pintype "passive"))
    )
  )
)
